# MultiDrop.net
KiCad netlist of a schematic drawn in EAGLE
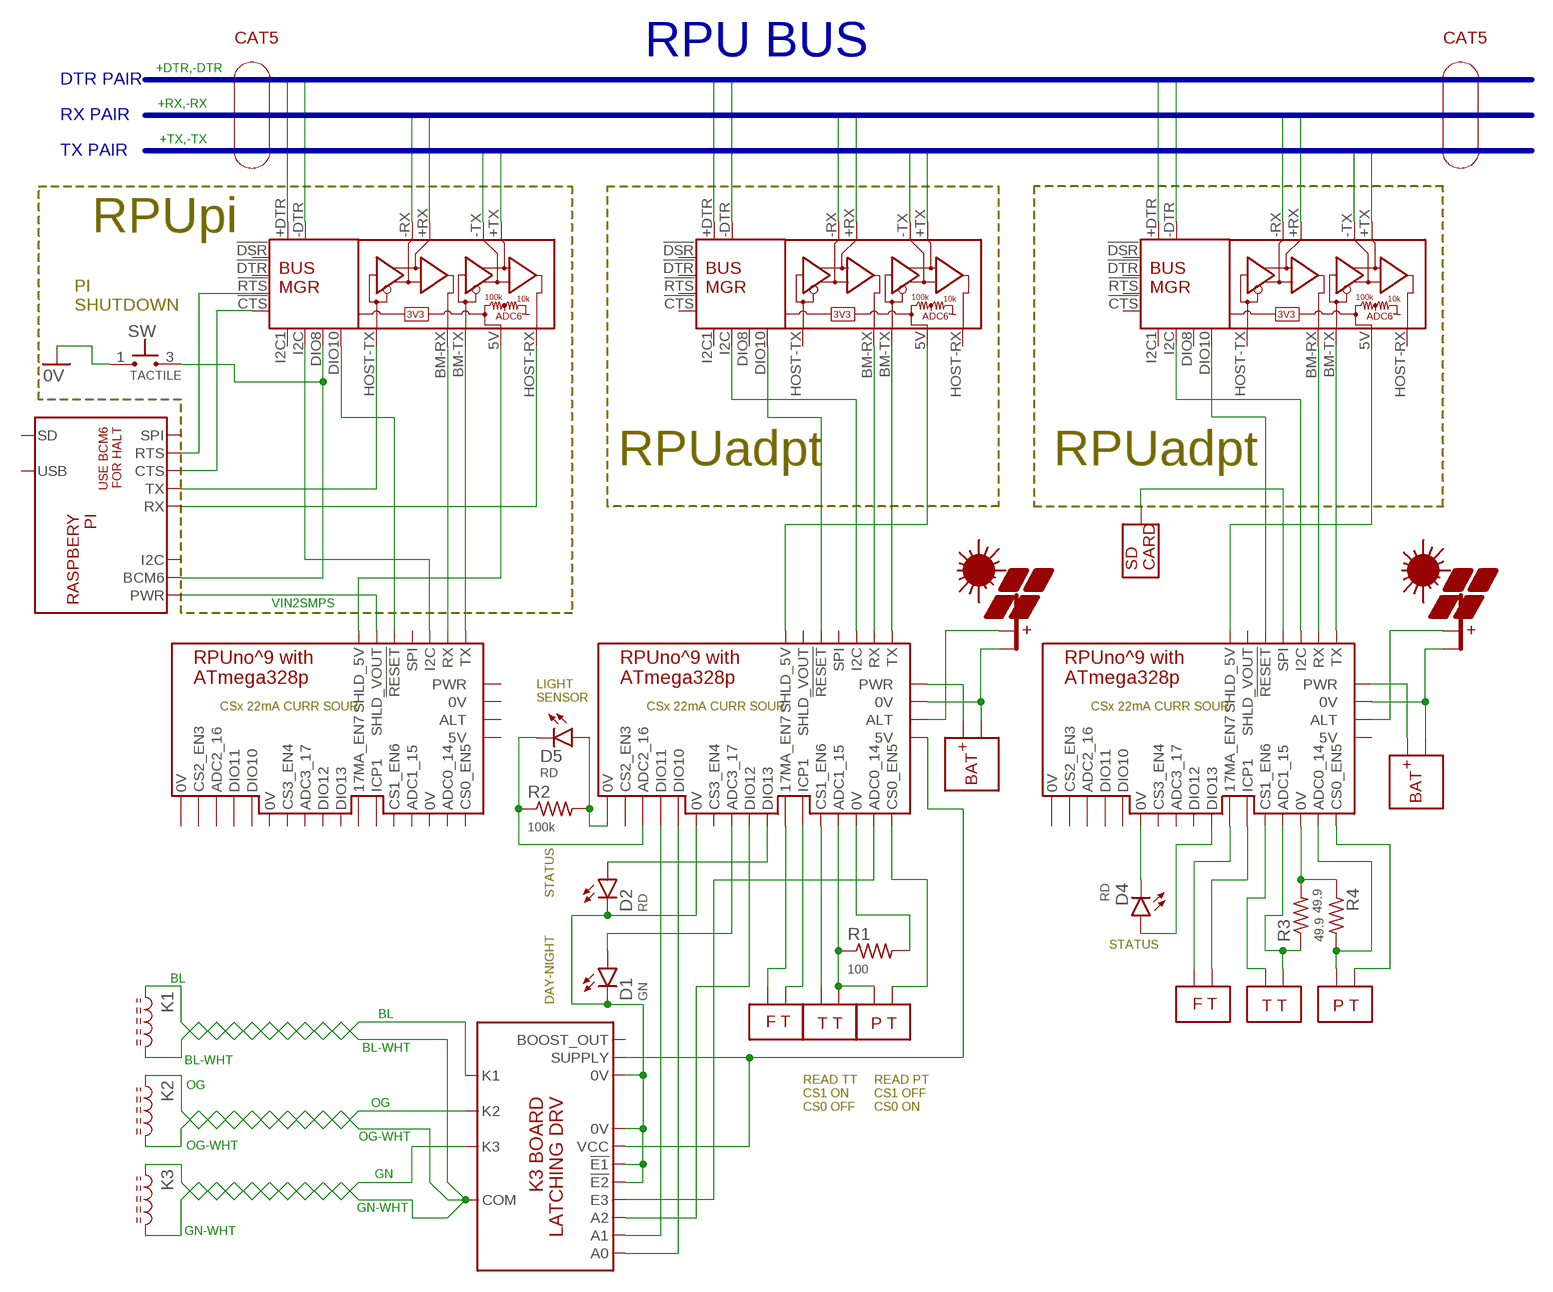
[diagram p0: schematic, sheet 1]

(export (version "E")
  (design (tool "Eeschema 10.0.6"))
  (components
    (comp (ref "BM1")
      (value "RPUNO")
      (footprint "eagle-import:NA-30")
      (libsource (lib "eagle-import") (part "RPUNO"))
    )
    (comp (ref "BM2")
      (value "RPUNO")
      (footprint "eagle-import:NA-30")
      (libsource (lib "eagle-import") (part "RPUNO"))
    )
    (comp (ref "BM3")
      (value "RPUNO")
      (footprint "eagle-import:NA-30")
      (libsource (lib "eagle-import") (part "RPUNO"))
    )
    (comp (ref "D1")
      (value "GN")
      (footprint "eagle-import:LED5MM")
      (libsource (lib "eagle-import") (part "LED5MM"))
    )
    (comp (ref "D2")
      (value "RD")
      (footprint "eagle-import:LED5MM")
      (libsource (lib "eagle-import") (part "LED5MM"))
    )
    (comp (ref "D4")
      (value "RD")
      (footprint "eagle-import:LED5MM")
      (libsource (lib "eagle-import") (part "LED5MM"))
    )
    (comp (ref "D5")
      (value "RD")
      (footprint "eagle-import:LED5MM")
      (libsource (lib "eagle-import") (part "LED5MM"))
    )
    (comp (ref "K1")
      (value "L0805")
      (footprint "eagle-import:C0805(2012)")
      (libsource (lib "eagle-import") (part "L0805"))
    )
    (comp (ref "K2")
      (value "L0805")
      (footprint "eagle-import:C0805(2012)")
      (libsource (lib "eagle-import") (part "L0805"))
    )
    (comp (ref "K3")
      (value "L0805")
      (footprint "eagle-import:C0805(2012)")
      (libsource (lib "eagle-import") (part "L0805"))
    )
    (comp (ref "PV2")
      (value "PV")
      (footprint "eagle-import:NA-30")
      (libsource (lib "eagle-import") (part "PV"))
    )
    (comp (ref "PV4")
      (value "PV")
      (footprint "eagle-import:NA-30")
      (libsource (lib "eagle-import") (part "PV"))
    )
    (comp (ref "R1")
      (value "100")
      (footprint "eagle-import:C0805(2012)")
      (libsource (lib "eagle-import") (part "R0805"))
    )
    (comp (ref "R2")
      (value "100k")
      (footprint "eagle-import:C0805(2012)")
      (libsource (lib "eagle-import") (part "R0805"))
    )
    (comp (ref "R3")
      (value "49.9")
      (footprint "eagle-import:C0805(2012)")
      (libsource (lib "eagle-import") (part "R0805"))
    )
    (comp (ref "R4")
      (value "49.9")
      (footprint "eagle-import:C0805(2012)")
      (libsource (lib "eagle-import") (part "R0805"))
    )
    (comp (ref "SD2")
      (value "SD")
      (footprint "eagle-import:NA-30")
      (libsource (lib "eagle-import") (part "SD"))
    )
    (comp (ref "SW")
      (value "TACTILE")
      (footprint "eagle-import:KS11")
      (libsource (lib "eagle-import") (part "TAC_SW"))
    )
    (comp (ref "U$1")
      (value "BUS_MGR")
      (footprint "eagle-import:WITH_RPU_NAMES")
      (libsource (lib "eagle-import") (part "BUS_MGR"))
    )
    (comp (ref "U$2")
      (value "BUS_MGR")
      (footprint "eagle-import:WITH_RPU_NAMES")
      (libsource (lib "eagle-import") (part "BUS_MGR"))
    )
    (comp (ref "U$3")
      (value "BUS_MGR")
      (footprint "eagle-import:WITH_RPU_NAMES")
      (libsource (lib "eagle-import") (part "BUS_MGR"))
    )
    (comp (ref "U$4")
      (value "K3")
      (footprint "eagle-import:NA-30")
      (libsource (lib "eagle-import") (part "K3"))
    )
    (comp (ref "U$5")
      (value "FT")
      (footprint "eagle-import:NA-30")
      (libsource (lib "eagle-import") (part "FT"))
    )
    (comp (ref "U$6")
      (value "TT")
      (footprint "eagle-import:NA-30")
      (libsource (lib "eagle-import") (part "TT"))
    )
    (comp (ref "U$7")
      (value "BAT")
      (footprint "eagle-import:NA-30")
      (libsource (lib "eagle-import") (part "BAT"))
    )
    (comp (ref "U$8")
      (value "PT")
      (footprint "eagle-import:NA-30")
      (libsource (lib "eagle-import") (part "PT"))
    )
    (comp (ref "U$9")
      (value "BAT")
      (footprint "eagle-import:NA-30")
      (libsource (lib "eagle-import") (part "BAT"))
    )
    (comp (ref "U$10")
      (value "TT")
      (footprint "eagle-import:NA-30")
      (libsource (lib "eagle-import") (part "TT"))
    )
    (comp (ref "U$11")
      (value "PT")
      (footprint "eagle-import:NA-30")
      (libsource (lib "eagle-import") (part "PT"))
    )
    (comp (ref "U$12")
      (value "FT")
      (footprint "eagle-import:NA-30")
      (libsource (lib "eagle-import") (part "FT"))
    )
    (comp (ref "U$13")
      (value "PI")
      (footprint "eagle-import:NA-30")
      (libsource (lib "eagle-import") (part "PI"))
    )
  )
  (nets
    (net (code "7") (name "/BL") (class "Default")
      (node (ref "K1") (pin "1") (pinfunction "1_1") (pintype "passive"))
      (node (ref "U$4") (pin "11") (pinfunction "K1_11") (pintype "bidirectional"))
    )
    (net (code "8") (name "/BL-WHT") (class "Default")
      (node (ref "K1") (pin "2") (pinfunction "2_2") (pintype "passive"))
      (node (ref "U$4") (pin "9") (pinfunction "COM_9") (pintype "bidirectional"))
    )
    (net (code "9") (name "/GN") (class "Default")
      (node (ref "K3") (pin "1") (pinfunction "1_1") (pintype "passive"))
      (node (ref "U$4") (pin "13") (pinfunction "K3_13") (pintype "bidirectional"))
    )
    (net (code "10") (name "/GN-WHT") (class "Default")
      (node (ref "K3") (pin "2") (pinfunction "2_2") (pintype "passive"))
    )
    (net (code "11") (name "/OG") (class "Default")
      (node (ref "K2") (pin "1") (pinfunction "1_1") (pintype "passive"))
      (node (ref "U$4") (pin "12") (pinfunction "K2_12") (pintype "bidirectional"))
    )
    (net (code "12") (name "/OG-WHT") (class "Default")
      (node (ref "K2") (pin "2") (pinfunction "2_2") (pintype "passive"))
    )
    (net (code "13") (name "/VIN2SMPS") (class "Default")
      (node (ref "BM2") (pin "7") (pinfunction "SHLD_VOUT_7") (pintype "bidirectional"))
      (node (ref "U$13") (pin "12") (pinfunction "PWR_12") (pintype "bidirectional"))
    )
    (net (code "17") (name "0V") (class "Default")
      (node (ref "SW") (pin "1") (pinfunction "1_1") (pintype "passive"))
    )
    (net (code "18") (name "Net-(BM1-0V-Pad26)") (class "Default")
      (node (ref "BM1") (pin "26") (pinfunction "0V_26") (pintype "bidirectional"))
      (node (ref "R1") (pin "2") (pinfunction "2_2") (pintype "passive"))
    )
    (net (code "19") (name "Net-(BM1-0V-Pad27)") (class "Default")
      (node (ref "BM1") (pin "27") (pinfunction "0V_27") (pintype "bidirectional"))
      (node (ref "D5") (pin "A") (pinfunction "A_A") (pintype "passive"))
      (node (ref "R2") (pin "2") (pinfunction "2_2") (pintype "passive"))
    )
    (net (code "20") (name "Net-(BM1-5V)") (class "Default")
      (node (ref "BM1") (pin "19") (pinfunction "5V_19") (pintype "bidirectional"))
      (node (ref "U$4") (pin "14") (pinfunction "SUPPLY_14") (pintype "bidirectional"))
      (node (ref "U$4") (pin "15") (pinfunction "VCC_15") (pintype "bidirectional"))
    )
    (net (code "21") (name "Net-(BM1-17MA_EN7)") (class "Default")
      (node (ref "BM1") (pin "21") (pinfunction "17MA_EN7_21") (pintype "bidirectional"))
      (node (ref "U$5") (pin "2") (pinfunction "PWR_2") (pintype "bidirectional"))
    )
    (net (code "22") (name "Net-(BM1-ADC0_14)") (class "Default")
      (node (ref "BM1") (pin "11") (pinfunction "ADC0_14_11") (pintype "bidirectional"))
      (node (ref "U$4") (pin "10") (pinfunction "E3_10") (pintype "bidirectional"))
    )
    (net (code "23") (name "Net-(BM1-ADC1_15)") (class "Default")
      (node (ref "BM1") (pin "10") (pinfunction "ADC1_15_10") (pintype "bidirectional"))
      (node (ref "R1") (pin "1") (pinfunction "1_1") (pintype "passive"))
      (node (ref "U$11") (pin "2") (pinfunction "PWR_2") (pintype "bidirectional"))
      (node (ref "U$6") (pin "1") (pinfunction "4TO20_1") (pintype "bidirectional"))
    )
    (net (code "24") (name "Net-(BM1-ADC2_16)") (class "Default")
      (node (ref "BM1") (pin "13") (pinfunction "ADC2_16_13") (pintype "bidirectional"))
      (node (ref "D5") (pin "K") (pinfunction "K_K") (pintype "passive"))
      (node (ref "R2") (pin "1") (pinfunction "1_1") (pintype "passive"))
    )
    (net (code "25") (name "Net-(BM1-ADC3_17)") (class "Default")
      (node (ref "BM1") (pin "16") (pinfunction "ADC3_17_16") (pintype "bidirectional"))
      (node (ref "D1") (pin "A") (pinfunction "A_A") (pintype "passive"))
    )
    (net (code "26") (name "Net-(BM1-ALT)") (class "Default")
      (node (ref "BM1") (pin "20") (pinfunction "ALT_20") (pintype "bidirectional"))
      (node (ref "PV2") (pin "1") (pinfunction "+PV_1") (pintype "bidirectional"))
    )
    (net (code "27") (name "Net-(BM1-CS0_EN5)") (class "Default")
      (node (ref "BM1") (pin "23") (pinfunction "CS0_EN5_23") (pintype "bidirectional"))
      (node (ref "U$11") (pin "1") (pinfunction "4TO20_1") (pintype "bidirectional"))
    )
    (net (code "28") (name "Net-(BM1-CS1_EN6)") (class "Default")
      (node (ref "BM1") (pin "22") (pinfunction "CS1_EN6_22") (pintype "bidirectional"))
      (node (ref "U$6") (pin "2") (pinfunction "PWR_2") (pintype "bidirectional"))
    )
    (net (code "29") (name "Net-(BM1-DIO10)") (class "Default")
      (node (ref "BM1") (pin "15") (pinfunction "DIO10_15") (pintype "bidirectional"))
      (node (ref "U$4") (pin "5") (pinfunction "A0_5") (pintype "bidirectional"))
    )
    (net (code "30") (name "Net-(BM1-DIO11)") (class "Default")
      (node (ref "BM1") (pin "14") (pinfunction "DIO11_14") (pintype "bidirectional"))
      (node (ref "U$4") (pin "6") (pinfunction "A1_6") (pintype "bidirectional"))
    )
    (net (code "31") (name "Net-(BM1-DIO12)") (class "Default")
      (node (ref "BM1") (pin "17") (pinfunction "DIO12_17") (pintype "bidirectional"))
      (node (ref "U$4") (pin "7") (pinfunction "A2_7") (pintype "bidirectional"))
    )
    (net (code "32") (name "Net-(BM1-DIO13)") (class "Default")
      (node (ref "BM1") (pin "18") (pinfunction "DIO13_18") (pintype "bidirectional"))
      (node (ref "D2") (pin "A") (pinfunction "A_A") (pintype "passive"))
    )
    (net (code "33") (name "Net-(BM1-I2C)") (class "Default")
      (node (ref "BM1") (pin "3") (pinfunction "I2C_3") (pintype "bidirectional"))
      (node (ref "U$2") (pin "I2C") (pinfunction "I2C_I2C") (pintype "bidirectional"))
    )
    (net (code "34") (name "Net-(BM1-ICP1)") (class "Default")
      (node (ref "BM1") (pin "12") (pinfunction "ICP1_12") (pintype "bidirectional"))
      (node (ref "U$5") (pin "1") (pinfunction "PL_1") (pintype "bidirectional"))
    )
    (net (code "35") (name "Net-(BM1-PWR)") (class "Default")
      (node (ref "BM1") (pin "8") (pinfunction "PWR_8") (pintype "bidirectional"))
      (node (ref "U$9") (pin "1") (pinfunction "+BAT_1") (pintype "bidirectional"))
    )
    (net (code "36") (name "Net-(BM1-RX)") (class "Default")
      (node (ref "BM1") (pin "2") (pinfunction "RX_2") (pintype "bidirectional"))
      (node (ref "U$2") (pin "BM-RX") (pinfunction "BM_RX_BM-RX") (pintype "bidirectional"))
    )
    (net (code "37") (name "Net-(BM1-SHLD_5V)") (class "Default")
      (node (ref "BM1") (pin "6") (pinfunction "SHLD_5V_6") (pintype "bidirectional"))
      (node (ref "U$2") (pin "5V") (pinfunction "PWR_5V") (pintype "bidirectional"))
    )
    (net (code "38") (name "Net-(BM1-TX)") (class "Default")
      (node (ref "BM1") (pin "1") (pinfunction "TX_1") (pintype "bidirectional"))
      (node (ref "U$2") (pin "BM-TX") (pinfunction "BM_TX_BM-TX") (pintype "bidirectional"))
    )
    (net (code "39") (name "Net-(BM1-~{RESET})") (class "Default")
      (node (ref "BM1") (pin "5") (pinfunction "~{RESET}_5") (pintype "bidirectional"))
      (node (ref "U$2") (pin "DIO10") (pinfunction "DIO10_DIO10") (pintype "bidirectional"))
    )
    (net (code "40") (name "Net-(BM2-I2C)") (class "Default")
      (node (ref "BM2") (pin "3") (pinfunction "I2C_3") (pintype "bidirectional"))
      (node (ref "U$3") (pin "I2C") (pinfunction "I2C_I2C") (pintype "bidirectional"))
    )
    (net (code "41") (name "Net-(BM2-RX)") (class "Default")
      (node (ref "BM2") (pin "2") (pinfunction "RX_2") (pintype "bidirectional"))
      (node (ref "U$3") (pin "BM-RX") (pinfunction "BM_RX_BM-RX") (pintype "bidirectional"))
    )
    (net (code "42") (name "Net-(BM2-SHLD_5V)") (class "Default")
      (node (ref "BM2") (pin "6") (pinfunction "SHLD_5V_6") (pintype "bidirectional"))
      (node (ref "U$3") (pin "5V") (pinfunction "PWR_5V") (pintype "bidirectional"))
    )
    (net (code "43") (name "Net-(BM2-TX)") (class "Default")
      (node (ref "BM2") (pin "1") (pinfunction "TX_1") (pintype "bidirectional"))
      (node (ref "U$3") (pin "BM-TX") (pinfunction "BM_TX_BM-TX") (pintype "bidirectional"))
    )
    (net (code "44") (name "Net-(BM2-~{RESET})") (class "Default")
      (node (ref "BM2") (pin "5") (pinfunction "~{RESET}_5") (pintype "bidirectional"))
      (node (ref "U$3") (pin "DIO10") (pinfunction "DIO10_DIO10") (pintype "bidirectional"))
    )
    (net (code "45") (name "Net-(BM3-0V-Pad26)") (class "Default")
      (node (ref "BM3") (pin "26") (pinfunction "0V_26") (pintype "bidirectional"))
      (node (ref "R3") (pin "2") (pinfunction "2_2") (pintype "passive"))
      (node (ref "R4") (pin "1") (pinfunction "1_1") (pintype "passive"))
    )
    (net (code "46") (name "Net-(BM3-0V-Pad28)") (class "Default")
      (node (ref "BM3") (pin "28") (pinfunction "0V_28") (pintype "bidirectional"))
      (node (ref "D4") (pin "K") (pinfunction "K_K") (pintype "passive"))
    )
    (net (code "47") (name "Net-(BM3-17MA_EN7)") (class "Default")
      (node (ref "BM3") (pin "21") (pinfunction "17MA_EN7_21") (pintype "bidirectional"))
      (node (ref "U$12") (pin "2") (pinfunction "PWR_2") (pintype "bidirectional"))
    )
    (net (code "48") (name "Net-(BM3-ADC0_14)") (class "Default")
      (node (ref "BM3") (pin "11") (pinfunction "ADC0_14_11") (pintype "bidirectional"))
      (node (ref "R4") (pin "2") (pinfunction "2_2") (pintype "passive"))
      (node (ref "U$8") (pin "2") (pinfunction "PWR_2") (pintype "bidirectional"))
    )
    (net (code "49") (name "Net-(BM3-ADC1_15)") (class "Default")
      (node (ref "BM3") (pin "10") (pinfunction "ADC1_15_10") (pintype "bidirectional"))
      (node (ref "R3") (pin "1") (pinfunction "1_1") (pintype "passive"))
      (node (ref "U$10") (pin "1") (pinfunction "4TO20_1") (pintype "bidirectional"))
    )
    (net (code "50") (name "Net-(BM3-ALT)") (class "Default")
      (node (ref "BM3") (pin "20") (pinfunction "ALT_20") (pintype "bidirectional"))
      (node (ref "PV4") (pin "1") (pinfunction "+PV_1") (pintype "bidirectional"))
    )
    (net (code "51") (name "Net-(BM3-CS0_EN5)") (class "Default")
      (node (ref "BM3") (pin "23") (pinfunction "CS0_EN5_23") (pintype "bidirectional"))
      (node (ref "U$8") (pin "1") (pinfunction "4TO20_1") (pintype "bidirectional"))
    )
    (net (code "52") (name "Net-(BM3-CS1_EN6)") (class "Default")
      (node (ref "BM3") (pin "22") (pinfunction "CS1_EN6_22") (pintype "bidirectional"))
      (node (ref "U$10") (pin "2") (pinfunction "PWR_2") (pintype "bidirectional"))
    )
    (net (code "53") (name "Net-(BM3-DIO13)") (class "Default")
      (node (ref "BM3") (pin "18") (pinfunction "DIO13_18") (pintype "bidirectional"))
      (node (ref "D4") (pin "A") (pinfunction "A_A") (pintype "passive"))
    )
    (net (code "54") (name "Net-(BM3-I2C)") (class "Default")
      (node (ref "BM3") (pin "3") (pinfunction "I2C_3") (pintype "bidirectional"))
      (node (ref "U$1") (pin "I2C") (pinfunction "I2C_I2C") (pintype "bidirectional"))
    )
    (net (code "55") (name "Net-(BM3-ICP1)") (class "Default")
      (node (ref "BM3") (pin "12") (pinfunction "ICP1_12") (pintype "bidirectional"))
      (node (ref "U$12") (pin "1") (pinfunction "PL_1") (pintype "bidirectional"))
    )
    (net (code "56") (name "Net-(BM3-PWR)") (class "Default")
      (node (ref "BM3") (pin "8") (pinfunction "PWR_8") (pintype "bidirectional"))
      (node (ref "U$7") (pin "1") (pinfunction "+BAT_1") (pintype "bidirectional"))
    )
    (net (code "57") (name "Net-(BM3-RX)") (class "Default")
      (node (ref "BM3") (pin "2") (pinfunction "RX_2") (pintype "bidirectional"))
      (node (ref "U$1") (pin "BM-RX") (pinfunction "BM_RX_BM-RX") (pintype "bidirectional"))
    )
    (net (code "58") (name "Net-(BM3-SHLD_5V)") (class "Default")
      (node (ref "BM3") (pin "6") (pinfunction "SHLD_5V_6") (pintype "bidirectional"))
      (node (ref "U$1") (pin "5V") (pinfunction "PWR_5V") (pintype "bidirectional"))
    )
    (net (code "59") (name "Net-(BM3-SPI)") (class "Default")
      (node (ref "BM3") (pin "4") (pinfunction "SPI_4") (pintype "bidirectional"))
      (node (ref "SD2") (pin "1") (pinfunction "PV_PWR_1") (pintype "bidirectional"))
    )
    (net (code "60") (name "Net-(BM3-TX)") (class "Default")
      (node (ref "BM3") (pin "1") (pinfunction "TX_1") (pintype "bidirectional"))
      (node (ref "U$1") (pin "BM-TX") (pinfunction "BM_TX_BM-TX") (pintype "bidirectional"))
    )
    (net (code "61") (name "Net-(BM3-~{RESET})") (class "Default")
      (node (ref "BM3") (pin "5") (pinfunction "~{RESET}_5") (pintype "bidirectional"))
      (node (ref "U$1") (pin "DIO10") (pinfunction "DIO10_DIO10") (pintype "bidirectional"))
    )
    (net (code "62") (name "Net-(PV2--PV)") (class "Default")
      (node (ref "BM1") (pin "9") (pinfunction "0V_9") (pintype "bidirectional"))
      (node (ref "PV2") (pin "2") (pinfunction "-PV_2") (pintype "bidirectional"))
      (node (ref "U$9") (pin "2") (pinfunction "-BAT_2") (pintype "bidirectional"))
    )
    (net (code "63") (name "Net-(PV4--PV)") (class "Default")
      (node (ref "BM3") (pin "9") (pinfunction "0V_9") (pintype "bidirectional"))
      (node (ref "PV4") (pin "2") (pinfunction "-PV_2") (pintype "bidirectional"))
      (node (ref "U$7") (pin "2") (pinfunction "-BAT_2") (pintype "bidirectional"))
    )
    (net (code "64") (name "Net-(U$4-~{E1})") (class "Default")
      (node (ref "BM1") (pin "28") (pinfunction "0V_28") (pintype "bidirectional"))
      (node (ref "D1") (pin "K") (pinfunction "K_K") (pintype "passive"))
      (node (ref "D2") (pin "K") (pinfunction "K_K") (pintype "passive"))
      (node (ref "U$4") (pin "1") (pinfunction "~{E1}_1") (pintype "bidirectional"))
      (node (ref "U$4") (pin "2") (pinfunction "~{E2}_2") (pintype "bidirectional"))
      (node (ref "U$4") (pin "3") (pinfunction "0V_3") (pintype "bidirectional"))
      (node (ref "U$4") (pin "4") (pinfunction "0V_4") (pintype "bidirectional"))
    )
    (net (code "65") (name "Net-(U$13-BCM6)") (class "Default")
      (node (ref "SW") (pin "3") (pinfunction "3_3") (pintype "passive"))
      (node (ref "U$13") (pin "7") (pinfunction "BCM6_7") (pintype "bidirectional"))
      (node (ref "U$3") (pin "DIO8") (pinfunction "DIO8_DIO8") (pintype "bidirectional"))
    )
    (net (code "66") (name "Net-(U$13-CTS)") (class "Default")
      (node (ref "U$13") (pin "1") (pinfunction "CTS_1") (pintype "input"))
      (node (ref "U$3") (pin "!CTS") (pinfunction "~{CTS}_!CTS") (pintype "bidirectional"))
    )
    (net (code "67") (name "Net-(U$13-RTS)") (class "Default")
      (node (ref "U$13") (pin "2") (pinfunction "RTS_2") (pintype "input"))
      (node (ref "U$3") (pin "!RTS") (pinfunction "~{RTS}_!RTS") (pintype "bidirectional"))
    )
    (net (code "68") (name "Net-(U$13-RX)") (class "Default")
      (node (ref "U$13") (pin "3") (pinfunction "RX_3") (pintype "bidirectional"))
      (node (ref "U$3") (pin "HOST-RX") (pinfunction "HOST_RX_HOST-RX") (pintype "bidirectional"))
    )
    (net (code "69") (name "Net-(U$13-TX)") (class "Default")
      (node (ref "U$13") (pin "4") (pinfunction "TX_4") (pintype "bidirectional"))
      (node (ref "U$3") (pin "HOST-TX") (pinfunction "HOST_TX_HOST-TX") (pintype "bidirectional"))
    )
    (net (code "70") (name "unconnected-(BM1-CS2_EN3-Pad24)") (class "Default")
      (node (ref "BM1") (pin "24") (pinfunction "CS2_EN3_24") (pintype "bidirectional"))
    )
    (net (code "71") (name "unconnected-(BM1-CS3_EN4-Pad29)") (class "Default")
      (node (ref "BM1") (pin "29") (pinfunction "CS3_EN4_29") (pintype "bidirectional"))
    )
    (net (code "72") (name "unconnected-(BM1-SHLD_VOUT-Pad7)") (class "Default")
      (node (ref "BM1") (pin "7") (pinfunction "SHLD_VOUT_7") (pintype "bidirectional"))
    )
    (net (code "73") (name "unconnected-(BM1-SPI-Pad4)") (class "Default")
      (node (ref "BM1") (pin "4") (pinfunction "SPI_4") (pintype "bidirectional"))
    )
    (net (code "74") (name "unconnected-(BM2-0V-Pad9)") (class "Default")
      (node (ref "BM2") (pin "9") (pinfunction "0V_9") (pintype "bidirectional"))
    )
    (net (code "75") (name "unconnected-(BM2-0V-Pad26)") (class "Default")
      (node (ref "BM2") (pin "26") (pinfunction "0V_26") (pintype "bidirectional"))
    )
    (net (code "76") (name "unconnected-(BM2-0V-Pad27)") (class "Default")
      (node (ref "BM2") (pin "27") (pinfunction "0V_27") (pintype "bidirectional"))
    )
    (net (code "77") (name "unconnected-(BM2-0V-Pad28)") (class "Default")
      (node (ref "BM2") (pin "28") (pinfunction "0V_28") (pintype "bidirectional"))
    )
    (net (code "78") (name "unconnected-(BM2-5V-Pad19)") (class "Default")
      (node (ref "BM2") (pin "19") (pinfunction "5V_19") (pintype "bidirectional"))
    )
    (net (code "79") (name "unconnected-(BM2-17MA_EN7-Pad21)") (class "Default")
      (node (ref "BM2") (pin "21") (pinfunction "17MA_EN7_21") (pintype "bidirectional"))
    )
    (net (code "80") (name "unconnected-(BM2-ADC0_14-Pad11)") (class "Default")
      (node (ref "BM2") (pin "11") (pinfunction "ADC0_14_11") (pintype "bidirectional"))
    )
    (net (code "81") (name "unconnected-(BM2-ADC1_15-Pad10)") (class "Default")
      (node (ref "BM2") (pin "10") (pinfunction "ADC1_15_10") (pintype "bidirectional"))
    )
    (net (code "82") (name "unconnected-(BM2-ADC2_16-Pad13)") (class "Default")
      (node (ref "BM2") (pin "13") (pinfunction "ADC2_16_13") (pintype "bidirectional"))
    )
    (net (code "83") (name "unconnected-(BM2-ADC3_17-Pad16)") (class "Default")
      (node (ref "BM2") (pin "16") (pinfunction "ADC3_17_16") (pintype "bidirectional"))
    )
    (net (code "84") (name "unconnected-(BM2-ALT-Pad20)") (class "Default")
      (node (ref "BM2") (pin "20") (pinfunction "ALT_20") (pintype "bidirectional"))
    )
    (net (code "85") (name "unconnected-(BM2-CS0_EN5-Pad23)") (class "Default")
      (node (ref "BM2") (pin "23") (pinfunction "CS0_EN5_23") (pintype "bidirectional"))
    )
    (net (code "86") (name "unconnected-(BM2-CS1_EN6-Pad22)") (class "Default")
      (node (ref "BM2") (pin "22") (pinfunction "CS1_EN6_22") (pintype "bidirectional"))
    )
    (net (code "87") (name "unconnected-(BM2-CS2_EN3-Pad24)") (class "Default")
      (node (ref "BM2") (pin "24") (pinfunction "CS2_EN3_24") (pintype "bidirectional"))
    )
    (net (code "88") (name "unconnected-(BM2-CS3_EN4-Pad29)") (class "Default")
      (node (ref "BM2") (pin "29") (pinfunction "CS3_EN4_29") (pintype "bidirectional"))
    )
    (net (code "89") (name "unconnected-(BM2-DIO10-Pad15)") (class "Default")
      (node (ref "BM2") (pin "15") (pinfunction "DIO10_15") (pintype "bidirectional"))
    )
    (net (code "90") (name "unconnected-(BM2-DIO11-Pad14)") (class "Default")
      (node (ref "BM2") (pin "14") (pinfunction "DIO11_14") (pintype "bidirectional"))
    )
    (net (code "91") (name "unconnected-(BM2-DIO12-Pad17)") (class "Default")
      (node (ref "BM2") (pin "17") (pinfunction "DIO12_17") (pintype "bidirectional"))
    )
    (net (code "92") (name "unconnected-(BM2-DIO13-Pad18)") (class "Default")
      (node (ref "BM2") (pin "18") (pinfunction "DIO13_18") (pintype "bidirectional"))
    )
    (net (code "93") (name "unconnected-(BM2-ICP1-Pad12)") (class "Default")
      (node (ref "BM2") (pin "12") (pinfunction "ICP1_12") (pintype "bidirectional"))
    )
    (net (code "94") (name "unconnected-(BM2-PWR-Pad8)") (class "Default")
      (node (ref "BM2") (pin "8") (pinfunction "PWR_8") (pintype "bidirectional"))
    )
    (net (code "95") (name "unconnected-(BM2-SPI-Pad4)") (class "Default")
      (node (ref "BM2") (pin "4") (pinfunction "SPI_4") (pintype "bidirectional"))
    )
    (net (code "96") (name "unconnected-(BM3-0V-Pad27)") (class "Default")
      (node (ref "BM3") (pin "27") (pinfunction "0V_27") (pintype "bidirectional"))
    )
    (net (code "97") (name "unconnected-(BM3-5V-Pad19)") (class "Default")
      (node (ref "BM3") (pin "19") (pinfunction "5V_19") (pintype "bidirectional"))
    )
    (net (code "98") (name "unconnected-(BM3-ADC2_16-Pad13)") (class "Default")
      (node (ref "BM3") (pin "13") (pinfunction "ADC2_16_13") (pintype "bidirectional"))
    )
    (net (code "99") (name "unconnected-(BM3-ADC3_17-Pad16)") (class "Default")
      (node (ref "BM3") (pin "16") (pinfunction "ADC3_17_16") (pintype "bidirectional"))
    )
    (net (code "100") (name "unconnected-(BM3-CS2_EN3-Pad24)") (class "Default")
      (node (ref "BM3") (pin "24") (pinfunction "CS2_EN3_24") (pintype "bidirectional"))
    )
    (net (code "101") (name "unconnected-(BM3-CS3_EN4-Pad29)") (class "Default")
      (node (ref "BM3") (pin "29") (pinfunction "CS3_EN4_29") (pintype "bidirectional"))
    )
    (net (code "102") (name "unconnected-(BM3-DIO10-Pad15)") (class "Default")
      (node (ref "BM3") (pin "15") (pinfunction "DIO10_15") (pintype "bidirectional"))
    )
    (net (code "103") (name "unconnected-(BM3-DIO11-Pad14)") (class "Default")
      (node (ref "BM3") (pin "14") (pinfunction "DIO11_14") (pintype "bidirectional"))
    )
    (net (code "104") (name "unconnected-(BM3-DIO12-Pad17)") (class "Default")
      (node (ref "BM3") (pin "17") (pinfunction "DIO12_17") (pintype "bidirectional"))
    )
    (net (code "105") (name "unconnected-(BM3-SHLD_VOUT-Pad7)") (class "Default")
      (node (ref "BM3") (pin "7") (pinfunction "SHLD_VOUT_7") (pintype "bidirectional"))
    )
    (net (code "106") (name "unconnected-(U$1-HOST_RX-PadHOST-RX)") (class "Default")
      (node (ref "U$1") (pin "HOST-RX") (pinfunction "HOST_RX_HOST-RX") (pintype "bidirectional"))
    )
    (net (code "107") (name "unconnected-(U$1-HOST_TX-PadHOST-TX)") (class "Default")
      (node (ref "U$1") (pin "HOST-TX") (pinfunction "HOST_TX_HOST-TX") (pintype "bidirectional"))
    )
    (net (code "108") (name "unconnected-(U$1-Pad+DTR)") (class "Default")
      (node (ref "U$1") (pin "+DTR") (pinfunction "+DTR_+DTR") (pintype "bidirectional"))
    )
    (net (code "109") (name "unconnected-(U$1-Pad+RX)") (class "Default")
      (node (ref "U$1") (pin "+RX") (pinfunction "+RX_+RX") (pintype "bidirectional"))
    )
    (net (code "110") (name "unconnected-(U$1-Pad+TX)") (class "Default")
      (node (ref "U$1") (pin "+TX") (pinfunction "+TX_+TX") (pintype "bidirectional"))
    )
    (net (code "111") (name "unconnected-(U$1-Pad-DTR)") (class "Default")
      (node (ref "U$1") (pin "-DTR") (pinfunction "-DTR_-DTR") (pintype "bidirectional"))
    )
    (net (code "112") (name "unconnected-(U$1-Pad-RX)") (class "Default")
      (node (ref "U$1") (pin "-RX") (pinfunction "-RX_-RX") (pintype "bidirectional"))
    )
    (net (code "113") (name "unconnected-(U$1-Pad-TX)") (class "Default")
      (node (ref "U$1") (pin "-TX") (pinfunction "-TX_-TX") (pintype "bidirectional"))
    )
    (net (code "114") (name "unconnected-(U$1-PadDIO8)") (class "Default")
      (node (ref "U$1") (pin "DIO8") (pinfunction "DIO8_DIO8") (pintype "bidirectional"))
    )
    (net (code "115") (name "unconnected-(U$1-PadI2C1)") (class "Default")
      (node (ref "U$1") (pin "I2C1") (pinfunction "I2C1_I2C1") (pintype "bidirectional"))
    )
    (net (code "116") (name "unconnected-(U$1-~{CTS}-Pad!CTS)") (class "Default")
      (node (ref "U$1") (pin "!CTS") (pinfunction "~{CTS}_!CTS") (pintype "bidirectional"))
    )
    (net (code "117") (name "unconnected-(U$1-~{DSR}-Pad!DSR)") (class "Default")
      (node (ref "U$1") (pin "!DSR") (pinfunction "~{DSR}_!DSR") (pintype "bidirectional"))
    )
    (net (code "118") (name "unconnected-(U$1-~{DTR}-Pad!DTR)") (class "Default")
      (node (ref "U$1") (pin "!DTR") (pinfunction "~{DTR}_!DTR") (pintype "bidirectional"))
    )
    (net (code "119") (name "unconnected-(U$1-~{RTS}-Pad!RTS)") (class "Default")
      (node (ref "U$1") (pin "!RTS") (pinfunction "~{RTS}_!RTS") (pintype "bidirectional"))
    )
    (net (code "120") (name "unconnected-(U$2-HOST_RX-PadHOST-RX)") (class "Default")
      (node (ref "U$2") (pin "HOST-RX") (pinfunction "HOST_RX_HOST-RX") (pintype "bidirectional"))
    )
    (net (code "121") (name "unconnected-(U$2-HOST_TX-PadHOST-TX)") (class "Default")
      (node (ref "U$2") (pin "HOST-TX") (pinfunction "HOST_TX_HOST-TX") (pintype "bidirectional"))
    )
    (net (code "122") (name "unconnected-(U$2-Pad+DTR)") (class "Default")
      (node (ref "U$2") (pin "+DTR") (pinfunction "+DTR_+DTR") (pintype "bidirectional"))
    )
    (net (code "123") (name "unconnected-(U$2-Pad+RX)") (class "Default")
      (node (ref "U$2") (pin "+RX") (pinfunction "+RX_+RX") (pintype "bidirectional"))
    )
    (net (code "124") (name "unconnected-(U$2-Pad+TX)") (class "Default")
      (node (ref "U$2") (pin "+TX") (pinfunction "+TX_+TX") (pintype "bidirectional"))
    )
    (net (code "125") (name "unconnected-(U$2-Pad-DTR)") (class "Default")
      (node (ref "U$2") (pin "-DTR") (pinfunction "-DTR_-DTR") (pintype "bidirectional"))
    )
    (net (code "126") (name "unconnected-(U$2-Pad-RX)") (class "Default")
      (node (ref "U$2") (pin "-RX") (pinfunction "-RX_-RX") (pintype "bidirectional"))
    )
    (net (code "127") (name "unconnected-(U$2-Pad-TX)") (class "Default")
      (node (ref "U$2") (pin "-TX") (pinfunction "-TX_-TX") (pintype "bidirectional"))
    )
    (net (code "128") (name "unconnected-(U$2-PadDIO8)") (class "Default")
      (node (ref "U$2") (pin "DIO8") (pinfunction "DIO8_DIO8") (pintype "bidirectional"))
    )
    (net (code "129") (name "unconnected-(U$2-PadI2C1)") (class "Default")
      (node (ref "U$2") (pin "I2C1") (pinfunction "I2C1_I2C1") (pintype "bidirectional"))
    )
    (net (code "130") (name "unconnected-(U$2-~{CTS}-Pad!CTS)") (class "Default")
      (node (ref "U$2") (pin "!CTS") (pinfunction "~{CTS}_!CTS") (pintype "bidirectional"))
    )
    (net (code "131") (name "unconnected-(U$2-~{DSR}-Pad!DSR)") (class "Default")
      (node (ref "U$2") (pin "!DSR") (pinfunction "~{DSR}_!DSR") (pintype "bidirectional"))
    )
    (net (code "132") (name "unconnected-(U$2-~{DTR}-Pad!DTR)") (class "Default")
      (node (ref "U$2") (pin "!DTR") (pinfunction "~{DTR}_!DTR") (pintype "bidirectional"))
    )
    (net (code "133") (name "unconnected-(U$2-~{RTS}-Pad!RTS)") (class "Default")
      (node (ref "U$2") (pin "!RTS") (pinfunction "~{RTS}_!RTS") (pintype "bidirectional"))
    )
    (net (code "134") (name "unconnected-(U$3-Pad+DTR)") (class "Default")
      (node (ref "U$3") (pin "+DTR") (pinfunction "+DTR_+DTR") (pintype "bidirectional"))
    )
    (net (code "135") (name "unconnected-(U$3-Pad+RX)") (class "Default")
      (node (ref "U$3") (pin "+RX") (pinfunction "+RX_+RX") (pintype "bidirectional"))
    )
    (net (code "136") (name "unconnected-(U$3-Pad+TX)") (class "Default")
      (node (ref "U$3") (pin "+TX") (pinfunction "+TX_+TX") (pintype "bidirectional"))
    )
    (net (code "137") (name "unconnected-(U$3-Pad-DTR)") (class "Default")
      (node (ref "U$3") (pin "-DTR") (pinfunction "-DTR_-DTR") (pintype "bidirectional"))
    )
    (net (code "138") (name "unconnected-(U$3-Pad-RX)") (class "Default")
      (node (ref "U$3") (pin "-RX") (pinfunction "-RX_-RX") (pintype "bidirectional"))
    )
    (net (code "139") (name "unconnected-(U$3-Pad-TX)") (class "Default")
      (node (ref "U$3") (pin "-TX") (pinfunction "-TX_-TX") (pintype "bidirectional"))
    )
    (net (code "140") (name "unconnected-(U$3-PadI2C1)") (class "Default")
      (node (ref "U$3") (pin "I2C1") (pinfunction "I2C1_I2C1") (pintype "bidirectional"))
    )
    (net (code "141") (name "unconnected-(U$3-~{DSR}-Pad!DSR)") (class "Default")
      (node (ref "U$3") (pin "!DSR") (pinfunction "~{DSR}_!DSR") (pintype "bidirectional"))
    )
    (net (code "142") (name "unconnected-(U$3-~{DTR}-Pad!DTR)") (class "Default")
      (node (ref "U$3") (pin "!DTR") (pinfunction "~{DTR}_!DTR") (pintype "bidirectional"))
    )
    (net (code "143") (name "unconnected-(U$4-BOOST_OUT-Pad8)") (class "Default")
      (node (ref "U$4") (pin "8") (pinfunction "BOOST_OUT_8") (pintype "bidirectional"))
    )
    (net (code "144") (name "unconnected-(U$13-I2C-Pad8)") (class "Default")
      (node (ref "U$13") (pin "8") (pinfunction "I2C_8") (pintype "bidirectional"))
    )
    (net (code "145") (name "unconnected-(U$13-SD-Pad9)") (class "Default")
      (node (ref "U$13") (pin "9") (pinfunction "SD_9") (pintype "input"))
    )
    (net (code "146") (name "unconnected-(U$13-SPI-Pad10)") (class "Default")
      (node (ref "U$13") (pin "10") (pinfunction "SPI_10") (pintype "bidirectional"))
    )
    (net (code "147") (name "unconnected-(U$13-USB-Pad11)") (class "Default")
      (node (ref "U$13") (pin "11") (pinfunction "USB_11") (pintype "input"))
    )
  )
)
